# tree2.net
KiCad netlist of a schematic drawn in EAGLE
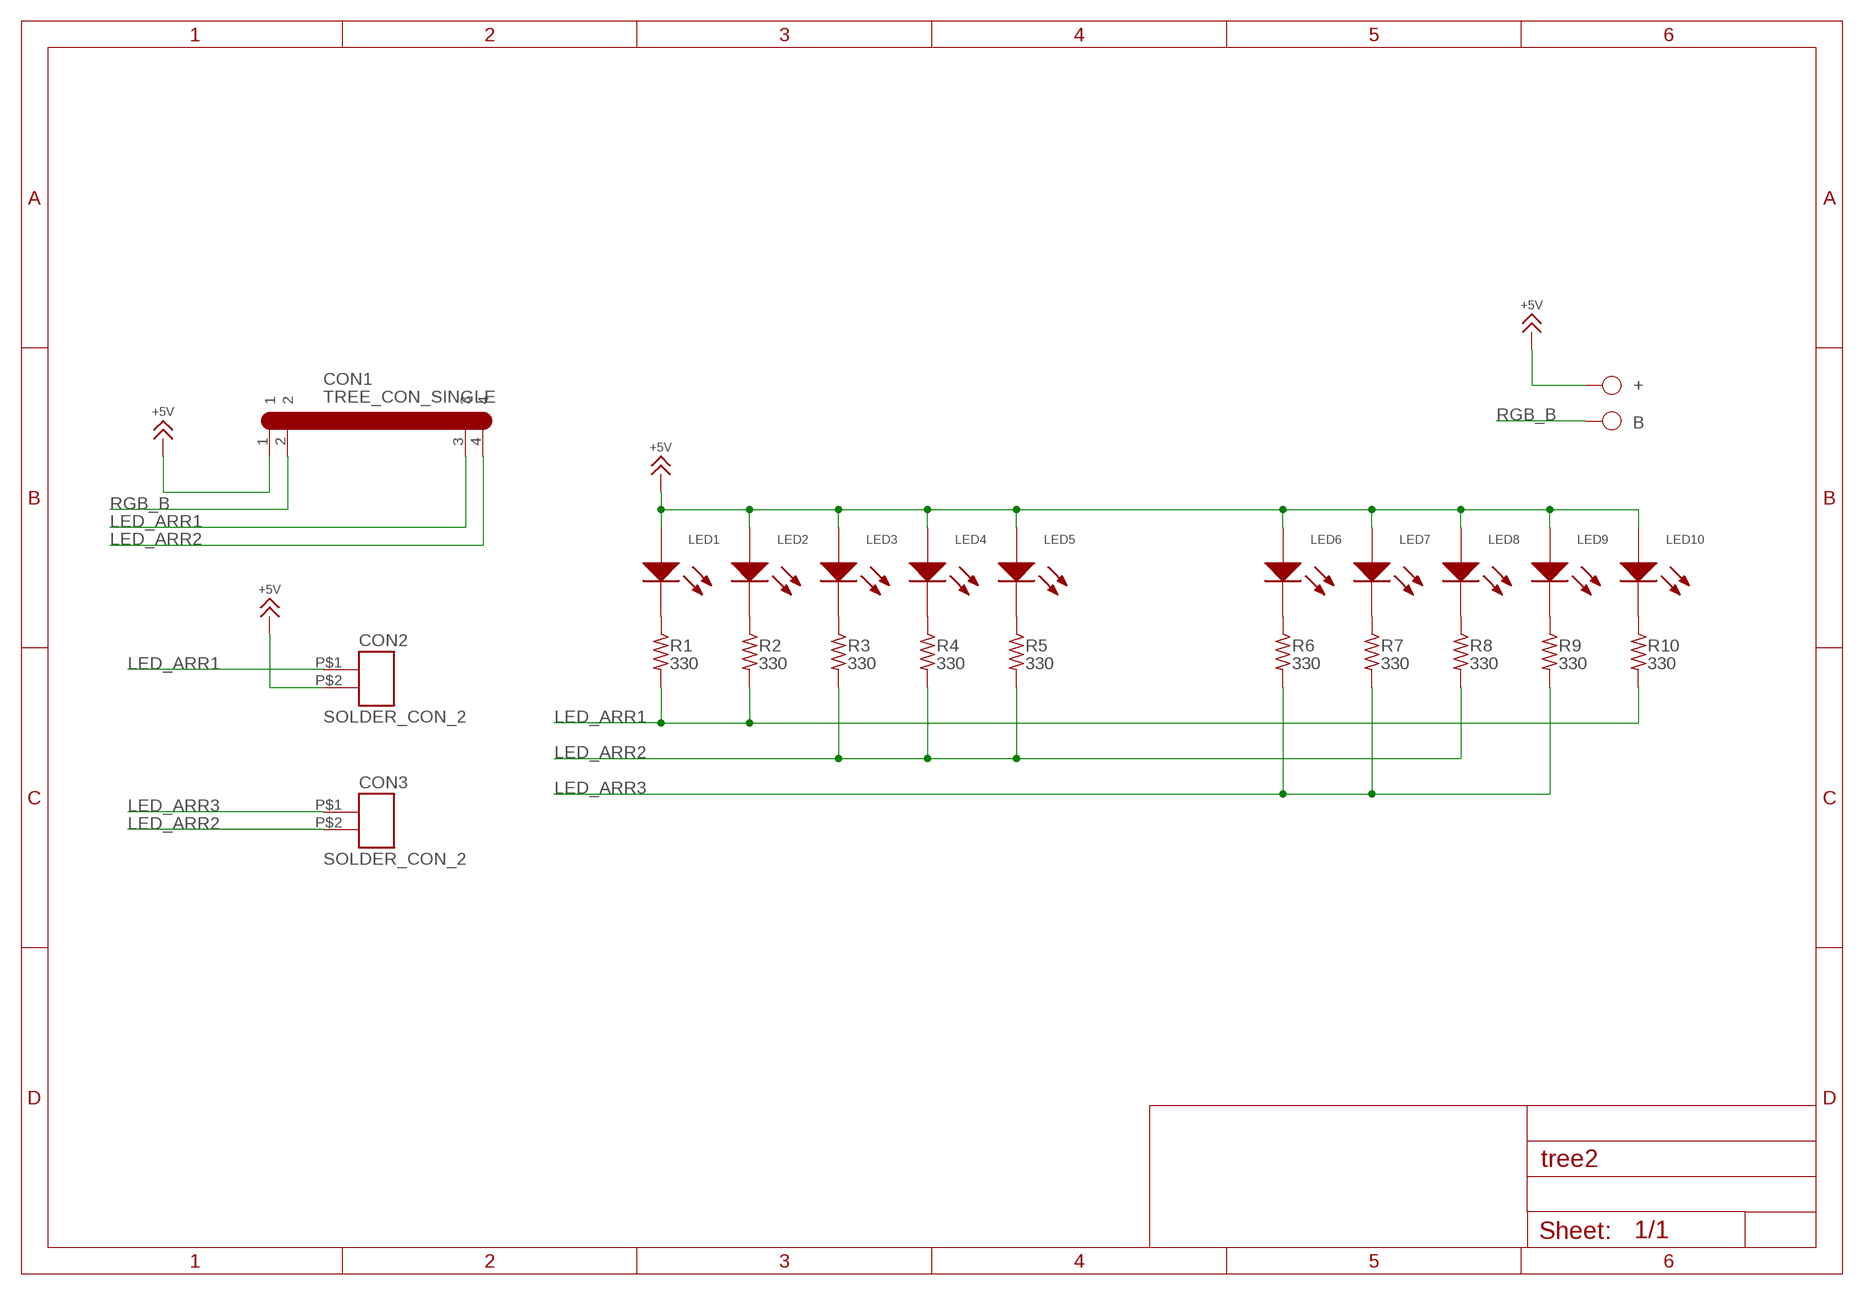
[diagram p0: schematic, sheet 1]

(export (version "E")
  (design (tool "Eeschema 10.0.6"))
  (components
    (comp (ref "+") (value "TP") (footprint "eagle-import:TP") (libsource (lib "eagle-import") (part "TP")))
    (comp (ref "B") (value "TP") (footprint "eagle-import:TP") (libsource (lib "eagle-import") (part "TP")))
    (comp (ref "CON1")
      (value "TREE_CON_SINGLE")
      (footprint "eagle-import:TREE_CON_SINGLE")
      (libsource (lib "eagle-import") (part "TREE_CON_SINGLE"))
    )
    (comp (ref "CON2")
      (value "SOLDER_CON_2")
      (footprint "eagle-import:SOLDER_CON_2")
      (libsource (lib "eagle-import") (part "SOLDER_CON_2"))
    )
    (comp (ref "CON3")
      (value "SOLDER_CON_2")
      (footprint "eagle-import:SOLDER_CON_2")
      (libsource (lib "eagle-import") (part "SOLDER_CON_2"))
    )
    (comp (ref "LED1")
      (value "LED_BEN")
      (footprint "eagle-import:LED_5MM_BEN")
      (libsource (lib "eagle-import") (part "LED_BEN"))
    )
    (comp (ref "LED2")
      (value "LED_BEN")
      (footprint "eagle-import:LED_5MM_BEN")
      (libsource (lib "eagle-import") (part "LED_BEN"))
    )
    (comp (ref "LED3")
      (value "LED_BEN")
      (footprint "eagle-import:LED_5MM_BEN")
      (libsource (lib "eagle-import") (part "LED_BEN"))
    )
    (comp (ref "LED4")
      (value "LED_BEN")
      (footprint "eagle-import:LED_5MM_BEN")
      (libsource (lib "eagle-import") (part "LED_BEN"))
    )
    (comp (ref "LED5")
      (value "LED_BEN")
      (footprint "eagle-import:LED_5MM_BEN")
      (libsource (lib "eagle-import") (part "LED_BEN"))
    )
    (comp (ref "LED6")
      (value "LED_BEN")
      (footprint "eagle-import:LED_5MM_BEN")
      (libsource (lib "eagle-import") (part "LED_BEN"))
    )
    (comp (ref "LED7")
      (value "LED_BEN")
      (footprint "eagle-import:LED_5MM_BEN")
      (libsource (lib "eagle-import") (part "LED_BEN"))
    )
    (comp (ref "LED8")
      (value "LED_BEN")
      (footprint "eagle-import:LED_5MM_BEN")
      (libsource (lib "eagle-import") (part "LED_BEN"))
    )
    (comp (ref "LED9")
      (value "LED_BEN")
      (footprint "eagle-import:LED_5MM_BEN")
      (libsource (lib "eagle-import") (part "LED_BEN"))
    )
    (comp (ref "LED10")
      (value "LED_BEN")
      (footprint "eagle-import:LED_5MM_BEN")
      (libsource (lib "eagle-import") (part "LED_BEN"))
    )
    (comp (ref "R1")
      (value "330")
      (footprint "eagle-import:SMD2012")
      (libsource (lib "eagle-import") (part "RES_2012"))
    )
    (comp (ref "R2")
      (value "330")
      (footprint "eagle-import:SMD2012")
      (libsource (lib "eagle-import") (part "RES_2012"))
    )
    (comp (ref "R3")
      (value "330")
      (footprint "eagle-import:SMD2012")
      (libsource (lib "eagle-import") (part "RES_2012"))
    )
    (comp (ref "R4")
      (value "330")
      (footprint "eagle-import:SMD2012")
      (libsource (lib "eagle-import") (part "RES_2012"))
    )
    (comp (ref "R5")
      (value "330")
      (footprint "eagle-import:SMD2012")
      (libsource (lib "eagle-import") (part "RES_2012"))
    )
    (comp (ref "R6")
      (value "330")
      (footprint "eagle-import:SMD2012")
      (libsource (lib "eagle-import") (part "RES_2012"))
    )
    (comp (ref "R7")
      (value "330")
      (footprint "eagle-import:SMD2012")
      (libsource (lib "eagle-import") (part "RES_2012"))
    )
    (comp (ref "R8")
      (value "330")
      (footprint "eagle-import:SMD2012")
      (libsource (lib "eagle-import") (part "RES_2012"))
    )
    (comp (ref "R9")
      (value "330")
      (footprint "eagle-import:SMD2012")
      (libsource (lib "eagle-import") (part "RES_2012"))
    )
    (comp (ref "R10")
      (value "330")
      (footprint "eagle-import:SMD2012")
      (libsource (lib "eagle-import") (part "RES_2012"))
    )
  )
  (nets
    (net (code "1") (name "+5V") (class "Default")
      (node (ref "+") (pin "1") (pinfunction "P$1_1") (pintype "passive"))
      (node (ref "CON1") (pin "1") (pinfunction "1_1") (pintype "passive"))
      (node (ref "CON2") (pin "P$2") (pinfunction "P$2_P$2") (pintype "passive"))
      (node (ref "LED1") (pin "1") (pinfunction "P$1_1") (pintype "passive"))
      (node (ref "LED10") (pin "1") (pinfunction "P$1_1") (pintype "passive"))
      (node (ref "LED2") (pin "1") (pinfunction "P$1_1") (pintype "passive"))
      (node (ref "LED3") (pin "1") (pinfunction "P$1_1") (pintype "passive"))
      (node (ref "LED4") (pin "1") (pinfunction "P$1_1") (pintype "passive"))
      (node (ref "LED5") (pin "1") (pinfunction "P$1_1") (pintype "passive"))
      (node (ref "LED6") (pin "1") (pinfunction "P$1_1") (pintype "passive"))
      (node (ref "LED7") (pin "1") (pinfunction "P$1_1") (pintype "passive"))
      (node (ref "LED8") (pin "1") (pinfunction "P$1_1") (pintype "passive"))
      (node (ref "LED9") (pin "1") (pinfunction "P$1_1") (pintype "passive"))
    )
    (net (code "2") (name "/LED_ARR1") (class "Default")
      (node (ref "CON1") (pin "3") (pinfunction "3_3") (pintype "passive"))
      (node (ref "CON2") (pin "P$1") (pinfunction "P$1_P$1") (pintype "passive"))
      (node (ref "R1") (pin "2") (pinfunction "2_2") (pintype "passive"))
      (node (ref "R10") (pin "2") (pinfunction "2_2") (pintype "passive"))
      (node (ref "R2") (pin "2") (pinfunction "2_2") (pintype "passive"))
    )
    (net (code "3") (name "/LED_ARR2") (class "Default")
      (node (ref "CON1") (pin "4") (pinfunction "4_4") (pintype "passive"))
      (node (ref "CON3") (pin "P$2") (pinfunction "P$2_P$2") (pintype "passive"))
      (node (ref "R3") (pin "2") (pinfunction "2_2") (pintype "passive"))
      (node (ref "R4") (pin "2") (pinfunction "2_2") (pintype "passive"))
      (node (ref "R5") (pin "2") (pinfunction "2_2") (pintype "passive"))
      (node (ref "R8") (pin "2") (pinfunction "2_2") (pintype "passive"))
    )
    (net (code "4") (name "/LED_ARR3") (class "Default")
      (node (ref "CON3") (pin "P$1") (pinfunction "P$1_P$1") (pintype "passive"))
      (node (ref "R6") (pin "2") (pinfunction "2_2") (pintype "passive"))
      (node (ref "R7") (pin "2") (pinfunction "2_2") (pintype "passive"))
      (node (ref "R9") (pin "2") (pinfunction "2_2") (pintype "passive"))
    )
    (net (code "5") (name "/RGB_B") (class "Default")
      (node (ref "B") (pin "1") (pinfunction "P$1_1") (pintype "passive"))
      (node (ref "CON1") (pin "2") (pinfunction "2_2") (pintype "passive"))
    )
    (net (code "6") (name "Net-(LED1-P$2)") (class "Default")
      (node (ref "LED1") (pin "2") (pinfunction "P$2_2") (pintype "passive"))
      (node (ref "R1") (pin "1") (pinfunction "1_1") (pintype "passive"))
    )
    (net (code "7") (name "Net-(LED2-P$2)") (class "Default")
      (node (ref "LED2") (pin "2") (pinfunction "P$2_2") (pintype "passive"))
      (node (ref "R2") (pin "1") (pinfunction "1_1") (pintype "passive"))
    )
    (net (code "8") (name "Net-(LED3-P$2)") (class "Default")
      (node (ref "LED3") (pin "2") (pinfunction "P$2_2") (pintype "passive"))
      (node (ref "R3") (pin "1") (pinfunction "1_1") (pintype "passive"))
    )
    (net (code "9") (name "Net-(LED4-P$2)") (class "Default")
      (node (ref "LED4") (pin "2") (pinfunction "P$2_2") (pintype "passive"))
      (node (ref "R4") (pin "1") (pinfunction "1_1") (pintype "passive"))
    )
    (net (code "10") (name "Net-(LED5-P$2)") (class "Default")
      (node (ref "LED5") (pin "2") (pinfunction "P$2_2") (pintype "passive"))
      (node (ref "R5") (pin "1") (pinfunction "1_1") (pintype "passive"))
    )
    (net (code "11") (name "Net-(LED6-P$2)") (class "Default")
      (node (ref "LED6") (pin "2") (pinfunction "P$2_2") (pintype "passive"))
      (node (ref "R6") (pin "1") (pinfunction "1_1") (pintype "passive"))
    )
    (net (code "12") (name "Net-(LED7-P$2)") (class "Default")
      (node (ref "LED7") (pin "2") (pinfunction "P$2_2") (pintype "passive"))
      (node (ref "R7") (pin "1") (pinfunction "1_1") (pintype "passive"))
    )
    (net (code "13") (name "Net-(LED8-P$2)") (class "Default")
      (node (ref "LED8") (pin "2") (pinfunction "P$2_2") (pintype "passive"))
      (node (ref "R8") (pin "1") (pinfunction "1_1") (pintype "passive"))
    )
    (net (code "14") (name "Net-(LED9-P$2)") (class "Default")
      (node (ref "LED9") (pin "2") (pinfunction "P$2_2") (pintype "passive"))
      (node (ref "R9") (pin "1") (pinfunction "1_1") (pintype "passive"))
    )
    (net (code "15") (name "Net-(LED10-P$2)") (class "Default")
      (node (ref "LED10") (pin "2") (pinfunction "P$2_2") (pintype "passive"))
      (node (ref "R10") (pin "1") (pinfunction "1_1") (pintype "passive"))
    )
  )
)
